# Nano_PCB.net
KiCad netlist of a schematic drawn in Altium Designer
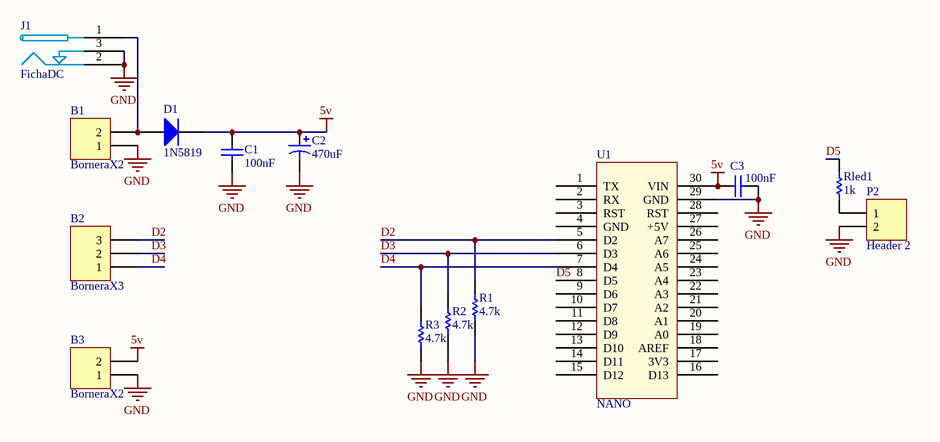
[diagram p0: Nano_PCB.SchDoc]

(export (version "E")
  (design (tool "Eeschema 10.0.6"))
  (components
    (comp (ref "B1")
      (value "BorneraX2")
      (footprint "BORx2-5mm")
      (libsource (lib "ComponentesBasicos") (part "BorneraX2"))
    )
    (comp (ref "B2")
      (value "BorneraX3")
      (footprint "BORx3-5mm")
      (libsource (lib "ComponentesBasicos") (part "BorneraX3"))
    )
    (comp (ref "B3")
      (value "BorneraX2")
      (footprint "BORx2-5mm")
      (libsource (lib "ComponentesBasicos") (part "BorneraX2"))
    )
    (comp (ref "C1")
      (value "100nF")
      (footprint "RAD-0.2")
      (description "Capacitor ceramico")
      (libsource (lib "ComponentesBasicos") (part "Capacitor ceramico"))
    )
    (comp (ref "C2")
      (value "470uF")
      (footprint "RAD-10.5-5mm")
      (description "Capacitor Electrolitico Polarizado")
      (libsource (lib "ComponentesBasicos") (part "Capacitor Elect.3 1000uF"))
    )
    (comp (ref "C3")
      (value "100nF")
      (footprint "C_0805")
      (description "0805 Ceramic Chip Capacitor")
      (libsource (lib "ComponentesBasicos") (part "Capacitor_0805"))
    )
    (comp (ref "D1")
      (value "1N5819")
      (footprint "DIODE-0.4")
      (description "1A Low Drop Power Schottky Rectifier Diode")
      (libsource (lib "ComponentesBasicos") (part "1N5819"))
    )
    (comp (ref "J1")
      (value "FichaDC")
      (footprint "FichaDC")
      (libsource (lib "ComponentesBasicos") (part "FichaDC"))
    )
    (comp (ref "P2")
      (value "Header 2")
      (footprint "HDR1X2")
      (description "Header, 2-Pin")
      (libsource (lib "ComponentesBasicos") (part "Header 2"))
    )
    (comp (ref "R1")
      (value "4.7k")
      (footprint "R_0805")
      (description "0805 1/8W Chip Resistor")
      (libsource (lib "ComponentesBasicos") (part "Resistor_0805"))
    )
    (comp (ref "R2")
      (value "4.7k")
      (footprint "R_0805")
      (description "0805 1/8W Chip Resistor")
      (libsource (lib "ComponentesBasicos") (part "Resistor_0805"))
    )
    (comp (ref "R3")
      (value "4.7k")
      (footprint "R_0805")
      (description "0805 1/8W Chip Resistor")
      (libsource (lib "ComponentesBasicos") (part "Resistor_0805"))
    )
    (comp (ref "Rled1")
      (value "1k")
      (footprint "R_0805")
      (description "0805 1/8W Chip Resistor")
      (libsource (lib "ComponentesBasicos") (part "Resistor_0805"))
    )
    (comp (ref "U1")
      (value "NANO")
      (footprint "NANO")
      (description "Arduino Nano")
      (libsource (lib "ComponentesBasicos") (part "NANO"))
    )
  )
  (nets
    (net (code "1") (name "/D2") (class "Default")
      (node (ref "B2") (pin "3") (pinfunction "3_3") (pintype "passive"))
      (node (ref "R1") (pin "2") (pinfunction "2_2") (pintype "passive"))
      (node (ref "U1") (pin "5") (pinfunction "D2_5") (pintype "passive"))
    )
    (net (code "2") (name "/D3") (class "Default")
      (node (ref "B2") (pin "2") (pinfunction "2_2") (pintype "passive"))
      (node (ref "R2") (pin "2") (pinfunction "2_2") (pintype "passive"))
      (node (ref "U1") (pin "6") (pinfunction "D3_6") (pintype "passive"))
    )
    (net (code "3") (name "/D4") (class "Default")
      (node (ref "B2") (pin "1") (pinfunction "1_1") (pintype "passive"))
      (node (ref "R3") (pin "2") (pinfunction "2_2") (pintype "passive"))
      (node (ref "U1") (pin "7") (pinfunction "D4_7") (pintype "passive"))
    )
    (net (code "4") (name "/D5") (class "Default")
      (node (ref "Rled1") (pin "1") (pinfunction "1_1") (pintype "passive"))
      (node (ref "U1") (pin "8") (pinfunction "D5_8") (pintype "passive"))
    )
    (net (code "5") (name "5v") (class "Default")
      (node (ref "B3") (pin "2") (pinfunction "2_2") (pintype "passive"))
      (node (ref "C1") (pin "2") (pinfunction "2_2") (pintype "passive"))
      (node (ref "C2") (pin "1") (pinfunction "1_1") (pintype "passive"))
      (node (ref "C3") (pin "1") (pinfunction "1_1") (pintype "passive"))
      (node (ref "D1") (pin "2") (pinfunction "K_2") (pintype "passive"))
      (node (ref "U1") (pin "30") (pinfunction "VIN_30") (pintype "passive"))
    )
    (net (code "6") (name "GND") (class "Default")
      (node (ref "B1") (pin "1") (pinfunction "1_1") (pintype "passive"))
      (node (ref "B3") (pin "1") (pinfunction "1_1") (pintype "passive"))
      (node (ref "C1") (pin "1") (pinfunction "1_1") (pintype "passive"))
      (node (ref "C2") (pin "2") (pinfunction "2_2") (pintype "passive"))
      (node (ref "C3") (pin "2") (pinfunction "2_2") (pintype "passive"))
      (node (ref "J1") (pin "2") (pintype "passive"))
      (node (ref "J1") (pin "3") (pintype "passive"))
      (node (ref "P2") (pin "2") (pinfunction "2_2") (pintype "passive"))
      (node (ref "R1") (pin "1") (pinfunction "1_1") (pintype "passive"))
      (node (ref "R2") (pin "1") (pinfunction "1_1") (pintype "passive"))
      (node (ref "R3") (pin "1") (pinfunction "1_1") (pintype "passive"))
      (node (ref "U1") (pin "29") (pinfunction "GND_29") (pintype "passive"))
    )
    (net (code "7") (name "Net-(D1-A)") (class "Default")
      (node (ref "B1") (pin "2") (pinfunction "2_2") (pintype "passive"))
      (node (ref "D1") (pin "1") (pinfunction "A_1") (pintype "passive"))
      (node (ref "J1") (pin "1") (pintype "passive"))
    )
    (net (code "8") (name "Net-(P2-Pad1)") (class "Default")
      (node (ref "P2") (pin "1") (pinfunction "1_1") (pintype "passive"))
      (node (ref "Rled1") (pin "2") (pinfunction "2_2") (pintype "passive"))
    )
    (net (code "9") (name "unconnected-(U1-+5V-Pad27)") (class "Default")
      (node (ref "U1") (pin "27") (pinfunction "+5V_27") (pintype "passive"))
    )
    (net (code "10") (name "unconnected-(U1-3V3-Pad17)") (class "Default")
      (node (ref "U1") (pin "17") (pinfunction "3V3_17") (pintype "passive"))
    )
    (net (code "11") (name "unconnected-(U1-A0-Pad19)") (class "Default")
      (node (ref "U1") (pin "19") (pinfunction "A0_19") (pintype "passive"))
    )
    (net (code "12") (name "unconnected-(U1-A1-Pad20)") (class "Default")
      (node (ref "U1") (pin "20") (pinfunction "A1_20") (pintype "passive"))
    )
    (net (code "13") (name "unconnected-(U1-A2-Pad21)") (class "Default")
      (node (ref "U1") (pin "21") (pinfunction "A2_21") (pintype "passive"))
    )
    (net (code "14") (name "unconnected-(U1-A3-Pad22)") (class "Default")
      (node (ref "U1") (pin "22") (pinfunction "A3_22") (pintype "passive"))
    )
    (net (code "15") (name "unconnected-(U1-A4-Pad23)") (class "Default")
      (node (ref "U1") (pin "23") (pinfunction "A4_23") (pintype "passive"))
    )
    (net (code "16") (name "unconnected-(U1-A5-Pad24)") (class "Default")
      (node (ref "U1") (pin "24") (pinfunction "A5_24") (pintype "passive"))
    )
    (net (code "17") (name "unconnected-(U1-A6-Pad25)") (class "Default")
      (node (ref "U1") (pin "25") (pinfunction "A6_25") (pintype "passive"))
    )
    (net (code "18") (name "unconnected-(U1-A7-Pad26)") (class "Default")
      (node (ref "U1") (pin "26") (pinfunction "A7_26") (pintype "passive"))
    )
    (net (code "19") (name "unconnected-(U1-AREF-Pad18)") (class "Default")
      (node (ref "U1") (pin "18") (pinfunction "AREF_18") (pintype "passive"))
    )
    (net (code "20") (name "unconnected-(U1-D6-Pad9)") (class "Default")
      (node (ref "U1") (pin "9") (pinfunction "D6_9") (pintype "passive"))
    )
    (net (code "21") (name "unconnected-(U1-D7-Pad10)") (class "Default")
      (node (ref "U1") (pin "10") (pinfunction "D7_10") (pintype "passive"))
    )
    (net (code "22") (name "unconnected-(U1-D8-Pad11)") (class "Default")
      (node (ref "U1") (pin "11") (pinfunction "D8_11") (pintype "passive"))
    )
    (net (code "23") (name "unconnected-(U1-D9-Pad12)") (class "Default")
      (node (ref "U1") (pin "12") (pinfunction "D9_12") (pintype "passive"))
    )
    (net (code "24") (name "unconnected-(U1-D10-Pad13)") (class "Default")
      (node (ref "U1") (pin "13") (pinfunction "D10_13") (pintype "passive"))
    )
    (net (code "25") (name "unconnected-(U1-D11-Pad14)") (class "Default")
      (node (ref "U1") (pin "14") (pinfunction "D11_14") (pintype "passive"))
    )
    (net (code "26") (name "unconnected-(U1-D12-Pad15)") (class "Default")
      (node (ref "U1") (pin "15") (pinfunction "D12_15") (pintype "passive"))
    )
    (net (code "27") (name "unconnected-(U1-D13-Pad16)") (class "Default")
      (node (ref "U1") (pin "16") (pinfunction "D13_16") (pintype "passive"))
    )
    (net (code "28") (name "unconnected-(U1-GND-Pad4)") (class "Default")
      (node (ref "U1") (pin "4") (pinfunction "GND_4") (pintype "passive"))
    )
    (net (code "29") (name "unconnected-(U1-RST-Pad3)") (class "Default")
      (node (ref "U1") (pin "3") (pinfunction "RST_3") (pintype "passive"))
    )
    (net (code "30") (name "unconnected-(U1-RST-Pad28)") (class "Default")
      (node (ref "U1") (pin "28") (pinfunction "RST_28") (pintype "passive"))
    )
    (net (code "31") (name "unconnected-(U1-RX-Pad2)") (class "Default")
      (node (ref "U1") (pin "2") (pinfunction "RX_2") (pintype "passive"))
    )
    (net (code "32") (name "unconnected-(U1-TX-Pad1)") (class "Default")
      (node (ref "U1") (pin "1") (pinfunction "TX_1") (pintype "passive"))
    )
  )
)
